# usbpd_input.net
KiCad netlist of a schematic drawn in Altium Designer
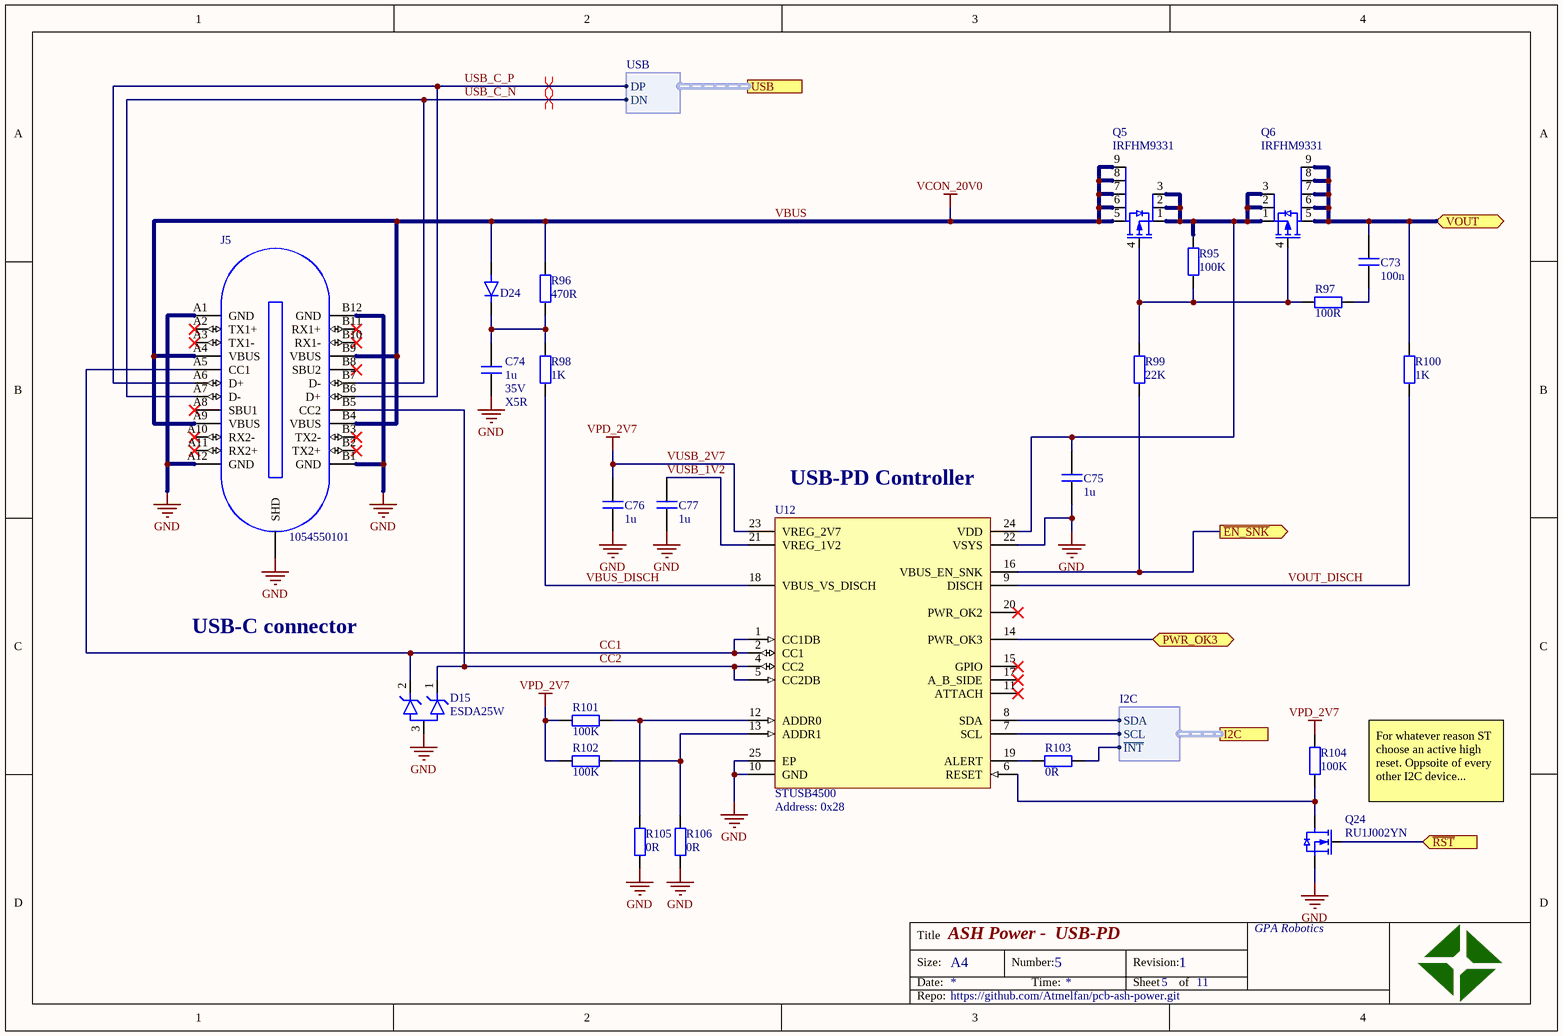
[diagram p0: usbpd_input.SchDoc]

(export (version "E")
  (design (tool "Eeschema 10.0.6"))
  (components
    (comp (ref "C73")
      (value "100n")
      (footprint "CAPC1005X06N")
      (description "Capacitor")
      (fields (field (name "Comment") "cap"))
      (libsource (lib "lib_passives") (part "cap"))
    )
    (comp (ref "C74")
      (value "1u")
      (footprint "CAPC2012X11N")
      (description "Capacitor")
      (fields (field (name "VOLTAGE") "35V") (field (name "TYPE") "X5R") (field (name "Comment") "cap"))
      (libsource (lib "lib_passives") (part "cap"))
    )
    (comp (ref "C75")
      (value "1u")
      (footprint "CAPC2012X11N")
      (description "Capacitor")
      (fields (field (name "Comment") "cap"))
      (libsource (lib "lib_passives") (part "cap"))
    )
    (comp (ref "C76")
      (value "1u")
      (footprint "CAPC2012X11N")
      (description "Capacitor")
      (fields (field (name "Comment") "cap"))
      (libsource (lib "lib_passives") (part "cap"))
    )
    (comp (ref "C77")
      (value "1u")
      (footprint "CAPC2012X11N")
      (description "Capacitor")
      (fields (field (name "Comment") "cap"))
      (libsource (lib "lib_passives") (part "cap"))
    )
    (comp (ref "D15")
      (value "ESDA25W")
      (footprint "SOT65P210X110-3N_SOT323-3L")
      (description "TRANSIL array for data protection")
      (libsource (lib "lib_st") (part "esda25w"))
    )
    (comp (ref "D24")
      (value "DFLS2100")
      (footprint "SODFL370X100-2N_DFLS2100")
      (description "2.0A HIGH VOLTAGE SCHOTTKY BARRIER RECTIFIER")
      (libsource (lib "lib_diodesinc") (part "dfls2100"))
    )
    (comp (ref "J5")
      (value "1054550101")
      (footprint "1054550101")
      (description "USB TYPE C REC MIDDLE MOUNT TYPE")
      (libsource (lib "lib_molex") (part "1054550101"))
    )
    (comp (ref "Q5")
      (value "IRFHM9331")
      (footprint "PQFN67P300X300X100-8N")
      (description "HEXFET Power MOSFET")
      (libsource (lib "lib_infineon") (part "irfhm9331"))
    )
    (comp (ref "Q6")
      (value "IRFHM9331")
      (footprint "PQFN67P300X300X100-8N")
      (description "HEXFET Power MOSFET")
      (libsource (lib "lib_infineon") (part "irfhm9331"))
    )
    (comp (ref "Q24")
      (value "RU1J002YN")
      (footprint "SOTFL65P210X105-3N")
      (description "N-channel 50V 200mA Small signal MOSFET")
      (libsource (lib "lib_rohm") (part "ru1j002yn"))
    )
    (comp (ref "R95")
      (value "100K")
      (footprint "RESC1005X04N")
      (description "Resistor")
      (fields (field (name "Comment") "res"))
      (libsource (lib "") (part "res_1"))
    )
    (comp (ref "R96")
      (value "470R")
      (footprint "RESC2012X06N")
      (description "Resistor")
      (fields (field (name "Comment") "res"))
      (libsource (lib "") (part "res_1"))
    )
    (comp (ref "R97")
      (value "100R")
      (footprint "RESC1005X04N")
      (description "Resistor")
      (fields (field (name "Comment") "res"))
      (libsource (lib "lib_passives") (part "res"))
    )
    (comp (ref "R98")
      (value "1K")
      (footprint "RESC2012X06N")
      (description "Resistor")
      (fields (field (name "Comment") "res"))
      (libsource (lib "") (part "res_1"))
    )
    (comp (ref "R99")
      (value "22K")
      (footprint "RESC1005X04N")
      (description "Resistor")
      (fields (field (name "Comment") "res"))
      (libsource (lib "") (part "res_1"))
    )
    (comp (ref "R100")
      (value "1K")
      (footprint "RESC1005X04N")
      (description "Resistor")
      (fields (field (name "Comment") "res"))
      (libsource (lib "") (part "res_1"))
    )
    (comp (ref "R101")
      (value "100K")
      (footprint "RESC1005X04N")
      (description "Resistor")
      (fields (field (name "Comment") "res"))
      (libsource (lib "lib_passives") (part "res"))
    )
    (comp (ref "R102")
      (value "100K")
      (footprint "RESC1005X04N")
      (description "Resistor")
      (fields (field (name "Comment") "res"))
      (libsource (lib "lib_passives") (part "res"))
    )
    (comp (ref "R103")
      (value "0R")
      (footprint "RESC1005X04N")
      (description "Resistor")
      (fields (field (name "Comment") "res"))
      (libsource (lib "lib_passives") (part "res"))
    )
    (comp (ref "R104")
      (value "100K")
      (footprint "RESC1005X04N")
      (description "Resistor")
      (fields (field (name "Comment") "res"))
      (libsource (lib "") (part "res_1"))
    )
    (comp (ref "R105")
      (value "0R")
      (footprint "RESC1005X04N")
      (description "Resistor")
      (fields (field (name "Comment") "res"))
      (libsource (lib "") (part "res_1"))
    )
    (comp (ref "R106")
      (value "0R")
      (footprint "RESC1005X04N")
      (description "Resistor")
      (fields (field (name "Comment") "res"))
      (libsource (lib "") (part "res_1"))
    )
    (comp (ref "U12")
      (value "STUSB4500")
      (footprint "QFN50P400X400X100_HS-25N-STUSB4500")
      (description "Standalone USB PD sink controller with short-to-VBUS protections")
      (fields (field (name "ADDRESS") "0x28"))
      (libsource (lib "lib_st") (part "stusb4500qtr"))
    )
  )
  (nets
    (net (code "3") (name "/CC1") (class "Default")
      (node (ref "D15") (pin "2") (pinfunction "2_2") (pintype "passive"))
      (node (ref "J5") (pin "A5") (pinfunction "CC1_A5") (pintype "passive"))
      (node (ref "U12") (pin "1") (pinfunction "CC1DB_1") (pintype "input"))
      (node (ref "U12") (pin "2") (pinfunction "CC1_2") (pintype "bidirectional"))
    )
    (net (code "4") (name "/CC2") (class "Default")
      (node (ref "D15") (pin "1") (pinfunction "1_1") (pintype "passive"))
      (node (ref "J5") (pin "B5") (pinfunction "CC2_B5") (pintype "passive"))
      (node (ref "U12") (pin "4") (pinfunction "CC2_4") (pintype "bidirectional"))
      (node (ref "U12") (pin "5") (pinfunction "CC2DB_5") (pintype "input"))
    )
    (net (code "5") (name "/EN_SNK") (class "Default")
      (node (ref "R99") (pin "1") (pinfunction "1_1") (pintype "passive"))
      (node (ref "U12") (pin "16") (pinfunction "VBUS_EN_SNK_16") (pintype "open_collector"))
    )
    (net (code "6") (name "/PWR_OK3") (class "Default")
      (node (ref "U12") (pin "14") (pinfunction "PWR_OK3_14") (pintype "open_collector"))
    )
    (net (code "7") (name "/RST") (class "Default")
      (node (ref "Q24") (pin "1") (pinfunction "G_1") (pintype "passive"))
    )
    (net (code "8") (name "/SCL") (class "Default")
      (node (ref "U12") (pin "7") (pinfunction "SCL_7") (pintype "open_collector"))
    )
    (net (code "9") (name "/SDA") (class "Default")
      (node (ref "U12") (pin "8") (pinfunction "SDA_8") (pintype "open_collector"))
    )
    (net (code "10") (name "/USB_C_N") (class "Default")
      (node (ref "J5") (pin "A7") (pinfunction "D-_A7") (pintype "bidirectional"))
      (node (ref "J5") (pin "B7") (pinfunction "D-_B7") (pintype "bidirectional"))
    )
    (net (code "11") (name "/USB_C_P") (class "Default")
      (node (ref "J5") (pin "A6") (pinfunction "D+_A6") (pintype "bidirectional"))
      (node (ref "J5") (pin "B6") (pinfunction "D+_B6") (pintype "bidirectional"))
    )
    (net (code "12") (name "/VBUS_DISCH") (class "Default")
      (node (ref "R98") (pin "1") (pinfunction "1_1") (pintype "passive"))
      (node (ref "U12") (pin "18") (pinfunction "VBUS_VS_DISCH_18") (pintype "open_collector"))
    )
    (net (code "13") (name "/VOUT") (class "Default")
      (node (ref "C73") (pin "2") (pinfunction "2_2") (pintype "passive"))
      (node (ref "Q6") (pin "5") (pinfunction "D_5") (pintype "passive"))
      (node (ref "Q6") (pin "6") (pinfunction "D_6") (pintype "passive"))
      (node (ref "Q6") (pin "7") (pinfunction "D_7") (pintype "passive"))
      (node (ref "Q6") (pin "8") (pinfunction "D_8") (pintype "passive"))
      (node (ref "Q6") (pin "9") (pinfunction "D_9") (pintype "passive"))
      (node (ref "R100") (pin "2") (pinfunction "2_2") (pintype "passive"))
    )
    (net (code "14") (name "/VOUT_DISCH") (class "Default")
      (node (ref "R100") (pin "1") (pinfunction "1_1") (pintype "passive"))
      (node (ref "U12") (pin "9") (pinfunction "DISCH_9") (pintype "open_collector"))
    )
    (net (code "15") (name "/VUSB_1V2") (class "Default")
      (node (ref "C77") (pin "2") (pinfunction "2_2") (pintype "passive"))
      (node (ref "U12") (pin "21") (pinfunction "VREG_1V2_21") (pintype "power_in"))
    )
    (net (code "18") (name "/~{INT}") (class "Default")
      (node (ref "R103") (pin "2") (pinfunction "2_2") (pintype "passive"))
    )
    (net (code "19") (name "GND") (class "Default")
      (node (ref "C74") (pin "1") (pinfunction "1_1") (pintype "passive"))
      (node (ref "C75") (pin "1") (pinfunction "1_1") (pintype "passive"))
      (node (ref "C76") (pin "1") (pinfunction "1_1") (pintype "passive"))
      (node (ref "C77") (pin "1") (pinfunction "1_1") (pintype "passive"))
      (node (ref "D15") (pin "3") (pinfunction "3_3") (pintype "passive"))
      (node (ref "J5") (pin "A1") (pinfunction "GND_A1") (pintype "power_in"))
      (node (ref "J5") (pin "A12") (pinfunction "GND_A12") (pintype "power_in"))
      (node (ref "J5") (pin "B1") (pinfunction "GND_B1") (pintype "power_in"))
      (node (ref "J5") (pin "B12") (pinfunction "GND_B12") (pintype "power_in"))
      (node (ref "J5") (pin "SHD") (pinfunction "SHD_SHD") (pintype "passive"))
      (node (ref "Q24") (pin "2") (pinfunction "S_2") (pintype "passive"))
      (node (ref "R105") (pin "1") (pinfunction "1_1") (pintype "passive"))
      (node (ref "R106") (pin "1") (pinfunction "1_1") (pintype "passive"))
      (node (ref "U12") (pin "10") (pinfunction "GND_10") (pintype "power_in"))
      (node (ref "U12") (pin "22") (pinfunction "VSYS_22") (pintype "power_in"))
      (node (ref "U12") (pin "25") (pinfunction "EP_25") (pintype "power_in"))
    )
    (net (code "20") (name "Net-(C73-Pad1)") (class "Default")
      (node (ref "C73") (pin "1") (pinfunction "1_1") (pintype "passive"))
      (node (ref "R97") (pin "2") (pinfunction "2_2") (pintype "passive"))
    )
    (net (code "21") (name "Net-(C74-Pad2)") (class "Default")
      (node (ref "C74") (pin "2") (pinfunction "2_2") (pintype "passive"))
      (node (ref "D24") (pin "C") (pinfunction "C_C") (pintype "passive"))
      (node (ref "R96") (pin "1") (pinfunction "1_1") (pintype "passive"))
      (node (ref "R98") (pin "2") (pinfunction "2_2") (pintype "passive"))
    )
    (net (code "22") (name "Net-(Q5-G)") (class "Default")
      (node (ref "Q5") (pin "4") (pinfunction "G_4") (pintype "passive"))
      (node (ref "Q6") (pin "4") (pinfunction "G_4") (pintype "passive"))
      (node (ref "R95") (pin "1") (pinfunction "1_1") (pintype "passive"))
      (node (ref "R97") (pin "1") (pinfunction "1_1") (pintype "passive"))
      (node (ref "R99") (pin "2") (pinfunction "2_2") (pintype "passive"))
    )
    (net (code "23") (name "Net-(Q24-D)") (class "Default")
      (node (ref "Q24") (pin "3") (pinfunction "D_3") (pintype "passive"))
      (node (ref "R104") (pin "1") (pinfunction "1_1") (pintype "passive"))
      (node (ref "U12") (pin "6") (pinfunction "RESET_6") (pintype "input"))
    )
    (net (code "24") (name "Net-(U12-ADDR0)") (class "Default")
      (node (ref "R101") (pin "2") (pinfunction "2_2") (pintype "passive"))
      (node (ref "R105") (pin "2") (pinfunction "2_2") (pintype "passive"))
      (node (ref "U12") (pin "12") (pinfunction "ADDR0_12") (pintype "input"))
    )
    (net (code "25") (name "Net-(U12-ADDR1)") (class "Default")
      (node (ref "R102") (pin "2") (pinfunction "2_2") (pintype "passive"))
      (node (ref "R106") (pin "2") (pinfunction "2_2") (pintype "passive"))
      (node (ref "U12") (pin "13") (pinfunction "ADDR1_13") (pintype "input"))
    )
    (net (code "26") (name "Net-(U12-ALERT)") (class "Default")
      (node (ref "R103") (pin "1") (pinfunction "1_1") (pintype "passive"))
      (node (ref "U12") (pin "19") (pinfunction "ALERT_19") (pintype "open_collector"))
    )
    (net (code "27") (name "Net-(U12-VDD)") (class "Default")
      (node (ref "C75") (pin "2") (pinfunction "2_2") (pintype "passive"))
      (node (ref "Q5") (pin "1") (pinfunction "S_1") (pintype "passive"))
      (node (ref "Q5") (pin "2") (pinfunction "S_2") (pintype "passive"))
      (node (ref "Q5") (pin "3") (pinfunction "S_3") (pintype "passive"))
      (node (ref "Q6") (pin "1") (pinfunction "S_1") (pintype "passive"))
      (node (ref "Q6") (pin "2") (pinfunction "S_2") (pintype "passive"))
      (node (ref "Q6") (pin "3") (pinfunction "S_3") (pintype "passive"))
      (node (ref "R95") (pin "2") (pinfunction "2_2") (pintype "passive"))
      (node (ref "U12") (pin "24") (pinfunction "VDD_24") (pintype "power_in"))
    )
    (net (code "28") (name "VCON_20V0") (class "Default")
      (node (ref "D24") (pin "A") (pinfunction "A_A") (pintype "passive"))
      (node (ref "J5") (pin "A4") (pinfunction "VBUS_A4") (pintype "power_in"))
      (node (ref "J5") (pin "A9") (pinfunction "VBUS_A9") (pintype "power_in"))
      (node (ref "J5") (pin "B4") (pinfunction "VBUS_B4") (pintype "power_in"))
      (node (ref "J5") (pin "B9") (pinfunction "VBUS_B9") (pintype "power_in"))
      (node (ref "Q5") (pin "5") (pinfunction "D_5") (pintype "passive"))
      (node (ref "Q5") (pin "6") (pinfunction "D_6") (pintype "passive"))
      (node (ref "Q5") (pin "7") (pinfunction "D_7") (pintype "passive"))
      (node (ref "Q5") (pin "8") (pinfunction "D_8") (pintype "passive"))
      (node (ref "Q5") (pin "9") (pinfunction "D_9") (pintype "passive"))
      (node (ref "R96") (pin "2") (pinfunction "2_2") (pintype "passive"))
    )
    (net (code "29") (name "VPD_2V7") (class "Default")
      (node (ref "C76") (pin "2") (pinfunction "2_2") (pintype "passive"))
      (node (ref "R101") (pin "1") (pinfunction "1_1") (pintype "passive"))
      (node (ref "R102") (pin "1") (pinfunction "1_1") (pintype "passive"))
      (node (ref "R104") (pin "2") (pinfunction "2_2") (pintype "passive"))
      (node (ref "U12") (pin "23") (pinfunction "VREG_2V7_23") (pintype "power_in"))
    )
    (net (code "30") (name "unconnected-(J5-RX1+-PadB11)") (class "Default")
      (node (ref "J5") (pin "B11") (pinfunction "RX1+_B11") (pintype "bidirectional+no_connect"))
    )
    (net (code "31") (name "unconnected-(J5-RX1--PadB10)") (class "Default")
      (node (ref "J5") (pin "B10") (pinfunction "RX1-_B10") (pintype "bidirectional+no_connect"))
    )
    (net (code "32") (name "unconnected-(J5-RX2+-PadA11)") (class "Default")
      (node (ref "J5") (pin "A11") (pinfunction "RX2+_A11") (pintype "bidirectional+no_connect"))
    )
    (net (code "33") (name "unconnected-(J5-RX2--PadA10)") (class "Default")
      (node (ref "J5") (pin "A10") (pinfunction "RX2-_A10") (pintype "bidirectional+no_connect"))
    )
    (net (code "34") (name "unconnected-(J5-SBU1-PadA8)") (class "Default")
      (node (ref "J5") (pin "A8") (pinfunction "SBU1_A8") (pintype "passive+no_connect"))
    )
    (net (code "35") (name "unconnected-(J5-SBU2-PadB8)") (class "Default")
      (node (ref "J5") (pin "B8") (pinfunction "SBU2_B8") (pintype "passive+no_connect"))
    )
    (net (code "36") (name "unconnected-(J5-TX1+-PadA2)") (class "Default")
      (node (ref "J5") (pin "A2") (pinfunction "TX1+_A2") (pintype "bidirectional+no_connect"))
    )
    (net (code "37") (name "unconnected-(J5-TX1--PadA3)") (class "Default")
      (node (ref "J5") (pin "A3") (pinfunction "TX1-_A3") (pintype "bidirectional+no_connect"))
    )
    (net (code "38") (name "unconnected-(J5-TX2+-PadB2)") (class "Default")
      (node (ref "J5") (pin "B2") (pinfunction "TX2+_B2") (pintype "bidirectional+no_connect"))
    )
    (net (code "39") (name "unconnected-(J5-TX2--PadB3)") (class "Default")
      (node (ref "J5") (pin "B3") (pinfunction "TX2-_B3") (pintype "bidirectional+no_connect"))
    )
    (net (code "40") (name "unconnected-(U12-ATTACH-Pad11)") (class "Default")
      (node (ref "U12") (pin "11") (pinfunction "ATTACH_11") (pintype "open_collector+no_connect"))
    )
    (net (code "41") (name "unconnected-(U12-A_B_SIDE-Pad17)") (class "Default")
      (node (ref "U12") (pin "17") (pinfunction "A_B_SIDE_17") (pintype "open_collector+no_connect"))
    )
    (net (code "42") (name "unconnected-(U12-GPIO-Pad15)") (class "Default")
      (node (ref "U12") (pin "15") (pinfunction "GPIO_15") (pintype "open_collector+no_connect"))
    )
    (net (code "43") (name "unconnected-(U12-PWR_OK2-Pad20)") (class "Default")
      (node (ref "U12") (pin "20") (pinfunction "PWR_OK2_20") (pintype "open_collector+no_connect"))
    )
  )
)
